# 8-Solenoid-Schematic.net
KiCad netlist of a schematic drawn in Altium Designer
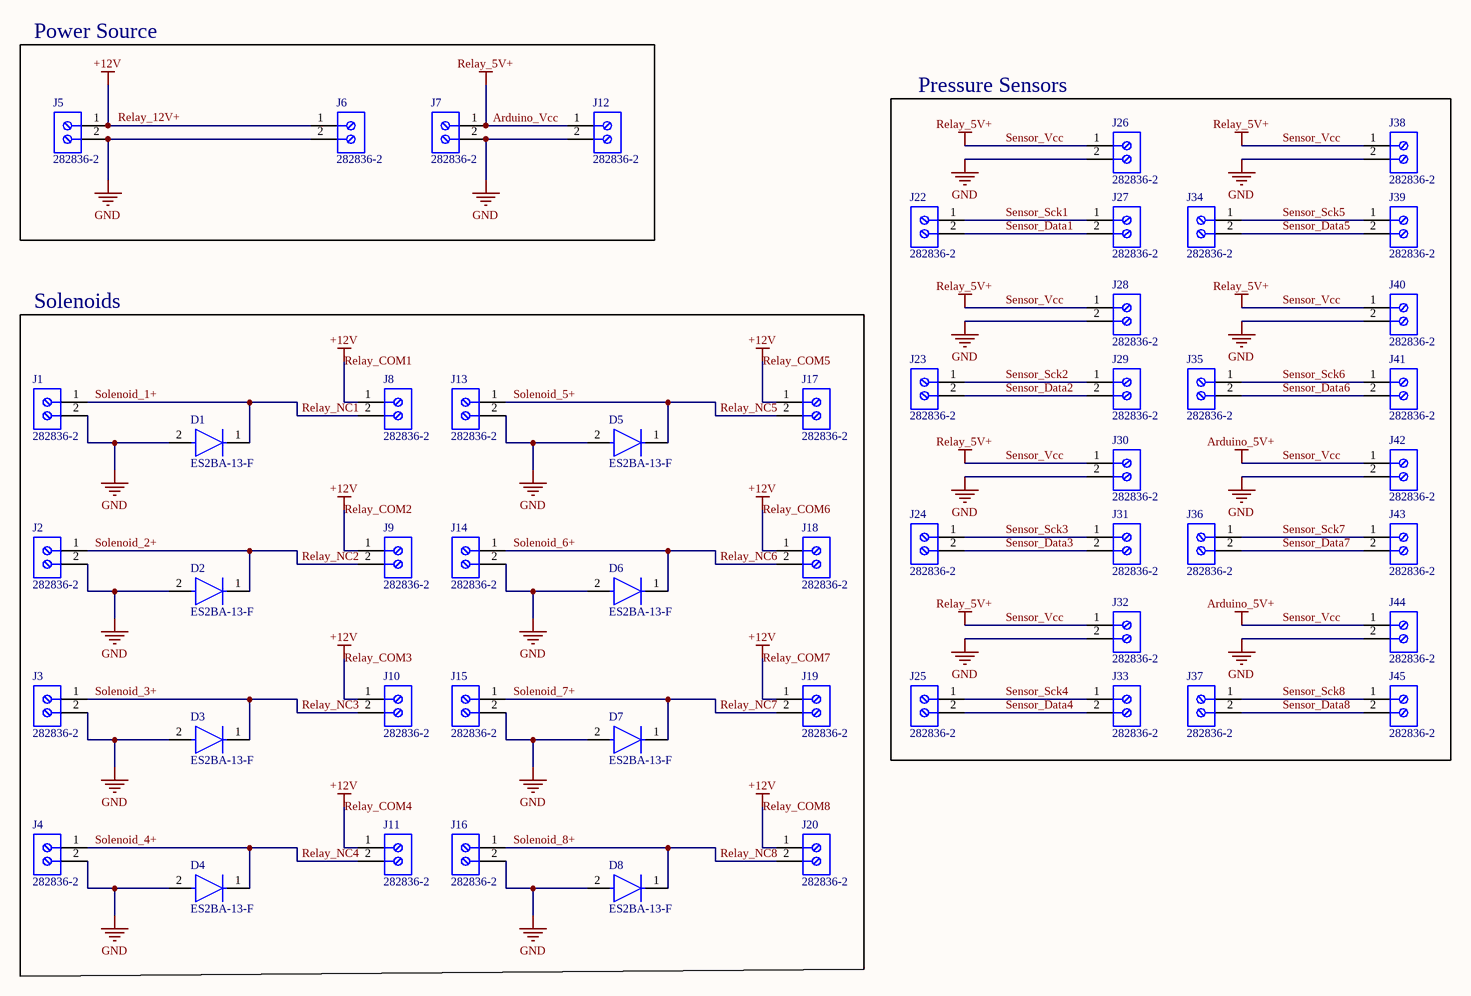
[diagram p0: 8-Solenoid-Schematic.SchDoc]

(export (version "E")
  (design (tool "Eeschema 10.0.6"))
  (components
    (comp (ref "D1")
      (value "ES2BA-13-F")
      (footprint "FP-SMA-MFG")
      (description "DIODE GEN PURP 100V 2A SMA")
      (fields
        (field (name "MANUFACTURER") "Diodes Inc.")
        (field (name "OCTOPART") "https://octopart.com/es2ba-13-f-diodes+inc.-14402013")
      )
      (libsource (lib "Altium Content Vault") (part "d7152d700b627762746794eb795d46e"))
    )
    (comp (ref "D2")
      (value "ES2BA-13-F")
      (footprint "FP-SMA-MFG")
      (description "DIODE GEN PURP 100V 2A SMA")
      (fields
        (field (name "MANUFACTURER") "Diodes Inc.")
        (field (name "OCTOPART") "https://octopart.com/es2ba-13-f-diodes+inc.-14402013")
      )
      (libsource (lib "Altium Content Vault") (part "d7152d700b627762746794eb795d46e"))
    )
    (comp (ref "D3")
      (value "ES2BA-13-F")
      (footprint "FP-SMA-MFG")
      (description "DIODE GEN PURP 100V 2A SMA")
      (fields
        (field (name "MANUFACTURER") "Diodes Inc.")
        (field (name "OCTOPART") "https://octopart.com/es2ba-13-f-diodes+inc.-14402013")
      )
      (libsource (lib "Altium Content Vault") (part "d7152d700b627762746794eb795d46e"))
    )
    (comp (ref "D4")
      (value "ES2BA-13-F")
      (footprint "FP-SMA-MFG")
      (description "DIODE GEN PURP 100V 2A SMA")
      (fields
        (field (name "MANUFACTURER") "Diodes Inc.")
        (field (name "OCTOPART") "https://octopart.com/es2ba-13-f-diodes+inc.-14402013")
      )
      (libsource (lib "Altium Content Vault") (part "d7152d700b627762746794eb795d46e"))
    )
    (comp (ref "D5")
      (value "ES2BA-13-F")
      (footprint "FP-SMA-MFG")
      (description "DIODE GEN PURP 100V 2A SMA")
      (fields
        (field (name "MANUFACTURER") "Diodes Inc.")
        (field (name "OCTOPART") "https://octopart.com/es2ba-13-f-diodes+inc.-14402013")
      )
      (libsource (lib "Altium Content Vault") (part "d7152d700b627762746794eb795d46e"))
    )
    (comp (ref "D6")
      (value "ES2BA-13-F")
      (footprint "FP-SMA-MFG")
      (description "DIODE GEN PURP 100V 2A SMA")
      (fields
        (field (name "MANUFACTURER") "Diodes Inc.")
        (field (name "OCTOPART") "https://octopart.com/es2ba-13-f-diodes+inc.-14402013")
      )
      (libsource (lib "Altium Content Vault") (part "d7152d700b627762746794eb795d46e"))
    )
    (comp (ref "D7")
      (value "ES2BA-13-F")
      (footprint "FP-SMA-MFG")
      (description "DIODE GEN PURP 100V 2A SMA")
      (fields
        (field (name "MANUFACTURER") "Diodes Inc.")
        (field (name "OCTOPART") "https://octopart.com/es2ba-13-f-diodes+inc.-14402013")
      )
      (libsource (lib "Altium Content Vault") (part "d7152d700b627762746794eb795d46e"))
    )
    (comp (ref "D8")
      (value "ES2BA-13-F")
      (footprint "FP-SMA-MFG")
      (description "DIODE GEN PURP 100V 2A SMA")
      (fields
        (field (name "MANUFACTURER") "Diodes Inc.")
        (field (name "OCTOPART") "https://octopart.com/es2ba-13-f-diodes+inc.-14402013")
      )
      (libsource (lib "Altium Content Vault") (part "d7152d700b627762746794eb795d46e"))
    )
    (comp (ref "J1")
      (value "282836-2")
      (footprint "TECO-282836-2_V")
      (description "Female Header, Pitch 5 mm, 1 x 2 Position, Height 10 mm, Tail Length 3.5 mm, Rohs, Bulk")
      (fields (field (name "VOLTAGE") "300V") (field (name "MANUFACTURER") "TE Connectivity"))
      (libsource (lib "Altium Content Vault") (part "CN-1P-F-TB2"))
    )
    (comp (ref "J2")
      (value "282836-2")
      (footprint "TECO-282836-2_V")
      (description "Female Header, Pitch 5 mm, 1 x 2 Position, Height 10 mm, Tail Length 3.5 mm, Rohs, Bulk")
      (fields (field (name "VOLTAGE") "300V") (field (name "MANUFACTURER") "TE Connectivity"))
      (libsource (lib "Altium Content Vault") (part "CN-1P-F-TB2"))
    )
    (comp (ref "J3")
      (value "282836-2")
      (footprint "TECO-282836-2_V")
      (description "Female Header, Pitch 5 mm, 1 x 2 Position, Height 10 mm, Tail Length 3.5 mm, Rohs, Bulk")
      (fields (field (name "VOLTAGE") "300V") (field (name "MANUFACTURER") "TE Connectivity"))
      (libsource (lib "Altium Content Vault") (part "CN-1P-F-TB2"))
    )
    (comp (ref "J4")
      (value "282836-2")
      (footprint "TECO-282836-2_V")
      (description "Female Header, Pitch 5 mm, 1 x 2 Position, Height 10 mm, Tail Length 3.5 mm, Rohs, Bulk")
      (fields (field (name "VOLTAGE") "300V") (field (name "MANUFACTURER") "TE Connectivity"))
      (libsource (lib "Altium Content Vault") (part "CN-1P-F-TB2"))
    )
    (comp (ref "J5")
      (value "282836-2")
      (footprint "TECO-282836-2_V")
      (description "Female Header, Pitch 5 mm, 1 x 2 Position, Height 10 mm, Tail Length 3.5 mm, Rohs, Bulk")
      (fields (field (name "VOLTAGE") "300V") (field (name "MANUFACTURER") "TE Connectivity"))
      (libsource (lib "Altium Content Vault") (part "CN-1P-F-TB2"))
    )
    (comp (ref "J6")
      (value "282836-2")
      (footprint "TECO-282836-2_V")
      (description "Female Header, Pitch 5 mm, 1 x 2 Position, Height 10 mm, Tail Length 3.5 mm, Rohs, Bulk")
      (fields (field (name "VOLTAGE") "300V") (field (name "MANUFACTURER") "TE Connectivity"))
      (libsource (lib "Altium Content Vault") (part "CN-1P-F-TB2"))
    )
    (comp (ref "J7")
      (value "282836-2")
      (footprint "TECO-282836-2_V")
      (description "Female Header, Pitch 5 mm, 1 x 2 Position, Height 10 mm, Tail Length 3.5 mm, Rohs, Bulk")
      (fields (field (name "VOLTAGE") "300V") (field (name "MANUFACTURER") "TE Connectivity"))
      (libsource (lib "Altium Content Vault") (part "CN-1P-F-TB2"))
    )
    (comp (ref "J8")
      (value "282836-2")
      (footprint "TECO-282836-2_V")
      (description "Female Header, Pitch 5 mm, 1 x 2 Position, Height 10 mm, Tail Length 3.5 mm, Rohs, Bulk")
      (fields (field (name "VOLTAGE") "300V") (field (name "MANUFACTURER") "TE Connectivity"))
      (libsource (lib "Altium Content Vault") (part "CN-1P-F-TB2"))
    )
    (comp (ref "J9")
      (value "282836-2")
      (footprint "TECO-282836-2_V")
      (description "Female Header, Pitch 5 mm, 1 x 2 Position, Height 10 mm, Tail Length 3.5 mm, Rohs, Bulk")
      (fields (field (name "VOLTAGE") "300V") (field (name "MANUFACTURER") "TE Connectivity"))
      (libsource (lib "Altium Content Vault") (part "CN-1P-F-TB2"))
    )
    (comp (ref "J10")
      (value "282836-2")
      (footprint "TECO-282836-2_V")
      (description "Female Header, Pitch 5 mm, 1 x 2 Position, Height 10 mm, Tail Length 3.5 mm, Rohs, Bulk")
      (fields (field (name "VOLTAGE") "300V") (field (name "MANUFACTURER") "TE Connectivity"))
      (libsource (lib "Altium Content Vault") (part "CN-1P-F-TB2"))
    )
    (comp (ref "J11")
      (value "282836-2")
      (footprint "TECO-282836-2_V")
      (description "Female Header, Pitch 5 mm, 1 x 2 Position, Height 10 mm, Tail Length 3.5 mm, Rohs, Bulk")
      (fields (field (name "VOLTAGE") "300V") (field (name "MANUFACTURER") "TE Connectivity"))
      (libsource (lib "Altium Content Vault") (part "CN-1P-F-TB2"))
    )
    (comp (ref "J12")
      (value "282836-2")
      (footprint "TECO-282836-2_V")
      (description "Female Header, Pitch 5 mm, 1 x 2 Position, Height 10 mm, Tail Length 3.5 mm, Rohs, Bulk")
      (fields (field (name "VOLTAGE") "300V") (field (name "MANUFACTURER") "TE Connectivity"))
      (libsource (lib "Altium Content Vault") (part "CN-1P-F-TB2"))
    )
    (comp (ref "J13")
      (value "282836-2")
      (footprint "TECO-282836-2_V")
      (description "Female Header, Pitch 5 mm, 1 x 2 Position, Height 10 mm, Tail Length 3.5 mm, Rohs, Bulk")
      (fields (field (name "VOLTAGE") "300V") (field (name "MANUFACTURER") "TE Connectivity"))
      (libsource (lib "Altium Content Vault") (part "CN-1P-F-TB2"))
    )
    (comp (ref "J14")
      (value "282836-2")
      (footprint "TECO-282836-2_V")
      (description "Female Header, Pitch 5 mm, 1 x 2 Position, Height 10 mm, Tail Length 3.5 mm, Rohs, Bulk")
      (fields (field (name "VOLTAGE") "300V") (field (name "MANUFACTURER") "TE Connectivity"))
      (libsource (lib "Altium Content Vault") (part "CN-1P-F-TB2"))
    )
    (comp (ref "J15")
      (value "282836-2")
      (footprint "TECO-282836-2_V")
      (description "Female Header, Pitch 5 mm, 1 x 2 Position, Height 10 mm, Tail Length 3.5 mm, Rohs, Bulk")
      (fields (field (name "VOLTAGE") "300V") (field (name "MANUFACTURER") "TE Connectivity"))
      (libsource (lib "Altium Content Vault") (part "CN-1P-F-TB2"))
    )
    (comp (ref "J16")
      (value "282836-2")
      (footprint "TECO-282836-2_V")
      (description "Female Header, Pitch 5 mm, 1 x 2 Position, Height 10 mm, Tail Length 3.5 mm, Rohs, Bulk")
      (fields (field (name "VOLTAGE") "300V") (field (name "MANUFACTURER") "TE Connectivity"))
      (libsource (lib "Altium Content Vault") (part "CN-1P-F-TB2"))
    )
    (comp (ref "J17")
      (value "282836-2")
      (footprint "TECO-282836-2_V")
      (description "Female Header, Pitch 5 mm, 1 x 2 Position, Height 10 mm, Tail Length 3.5 mm, Rohs, Bulk")
      (fields (field (name "VOLTAGE") "300V") (field (name "MANUFACTURER") "TE Connectivity"))
      (libsource (lib "Altium Content Vault") (part "CN-1P-F-TB2"))
    )
    (comp (ref "J18")
      (value "282836-2")
      (footprint "TECO-282836-2_V")
      (description "Female Header, Pitch 5 mm, 1 x 2 Position, Height 10 mm, Tail Length 3.5 mm, Rohs, Bulk")
      (fields (field (name "VOLTAGE") "300V") (field (name "MANUFACTURER") "TE Connectivity"))
      (libsource (lib "Altium Content Vault") (part "CN-1P-F-TB2"))
    )
    (comp (ref "J19")
      (value "282836-2")
      (footprint "TECO-282836-2_V")
      (description "Female Header, Pitch 5 mm, 1 x 2 Position, Height 10 mm, Tail Length 3.5 mm, Rohs, Bulk")
      (fields (field (name "VOLTAGE") "300V") (field (name "MANUFACTURER") "TE Connectivity"))
      (libsource (lib "Altium Content Vault") (part "CN-1P-F-TB2"))
    )
    (comp (ref "J20")
      (value "282836-2")
      (footprint "TECO-282836-2_V")
      (description "Female Header, Pitch 5 mm, 1 x 2 Position, Height 10 mm, Tail Length 3.5 mm, Rohs, Bulk")
      (fields (field (name "VOLTAGE") "300V") (field (name "MANUFACTURER") "TE Connectivity"))
      (libsource (lib "Altium Content Vault") (part "CN-1P-F-TB2"))
    )
    (comp (ref "J22")
      (value "282836-2")
      (footprint "TECO-282836-2_V")
      (description "Female Header, Pitch 5 mm, 1 x 2 Position, Height 10 mm, Tail Length 3.5 mm, Rohs, Bulk")
      (fields (field (name "VOLTAGE") "300V") (field (name "MANUFACTURER") "TE Connectivity"))
      (libsource (lib "Altium Content Vault") (part "CN-1P-F-TB2"))
    )
    (comp (ref "J23")
      (value "282836-2")
      (footprint "TECO-282836-2_V")
      (description "Female Header, Pitch 5 mm, 1 x 2 Position, Height 10 mm, Tail Length 3.5 mm, Rohs, Bulk")
      (fields (field (name "VOLTAGE") "300V") (field (name "MANUFACTURER") "TE Connectivity"))
      (libsource (lib "Altium Content Vault") (part "CN-1P-F-TB2"))
    )
    (comp (ref "J24")
      (value "282836-2")
      (footprint "TECO-282836-2_V")
      (description "Female Header, Pitch 5 mm, 1 x 2 Position, Height 10 mm, Tail Length 3.5 mm, Rohs, Bulk")
      (fields (field (name "VOLTAGE") "300V") (field (name "MANUFACTURER") "TE Connectivity"))
      (libsource (lib "Altium Content Vault") (part "CN-1P-F-TB2"))
    )
    (comp (ref "J25")
      (value "282836-2")
      (footprint "TECO-282836-2_V")
      (description "Female Header, Pitch 5 mm, 1 x 2 Position, Height 10 mm, Tail Length 3.5 mm, Rohs, Bulk")
      (fields (field (name "VOLTAGE") "300V") (field (name "MANUFACTURER") "TE Connectivity"))
      (libsource (lib "Altium Content Vault") (part "CN-1P-F-TB2"))
    )
    (comp (ref "J26")
      (value "282836-2")
      (footprint "TECO-282836-2_V")
      (description "Female Header, Pitch 5 mm, 1 x 2 Position, Height 10 mm, Tail Length 3.5 mm, Rohs, Bulk")
      (fields (field (name "VOLTAGE") "300V") (field (name "MANUFACTURER") "TE Connectivity"))
      (libsource (lib "Altium Content Vault") (part "CN-1P-F-TB2"))
    )
    (comp (ref "J27")
      (value "282836-2")
      (footprint "TECO-282836-2_V")
      (description "Female Header, Pitch 5 mm, 1 x 2 Position, Height 10 mm, Tail Length 3.5 mm, Rohs, Bulk")
      (fields (field (name "VOLTAGE") "300V") (field (name "MANUFACTURER") "TE Connectivity"))
      (libsource (lib "Altium Content Vault") (part "CN-1P-F-TB2"))
    )
    (comp (ref "J28")
      (value "282836-2")
      (footprint "TECO-282836-2_V")
      (description "Female Header, Pitch 5 mm, 1 x 2 Position, Height 10 mm, Tail Length 3.5 mm, Rohs, Bulk")
      (fields (field (name "VOLTAGE") "300V") (field (name "MANUFACTURER") "TE Connectivity"))
      (libsource (lib "Altium Content Vault") (part "CN-1P-F-TB2"))
    )
    (comp (ref "J29")
      (value "282836-2")
      (footprint "TECO-282836-2_V")
      (description "Female Header, Pitch 5 mm, 1 x 2 Position, Height 10 mm, Tail Length 3.5 mm, Rohs, Bulk")
      (fields (field (name "VOLTAGE") "300V") (field (name "MANUFACTURER") "TE Connectivity"))
      (libsource (lib "Altium Content Vault") (part "CN-1P-F-TB2"))
    )
    (comp (ref "J30")
      (value "282836-2")
      (footprint "TECO-282836-2_V")
      (description "Female Header, Pitch 5 mm, 1 x 2 Position, Height 10 mm, Tail Length 3.5 mm, Rohs, Bulk")
      (fields (field (name "VOLTAGE") "300V") (field (name "MANUFACTURER") "TE Connectivity"))
      (libsource (lib "Altium Content Vault") (part "CN-1P-F-TB2"))
    )
    (comp (ref "J31")
      (value "282836-2")
      (footprint "TECO-282836-2_V")
      (description "Female Header, Pitch 5 mm, 1 x 2 Position, Height 10 mm, Tail Length 3.5 mm, Rohs, Bulk")
      (fields (field (name "VOLTAGE") "300V") (field (name "MANUFACTURER") "TE Connectivity"))
      (libsource (lib "Altium Content Vault") (part "CN-1P-F-TB2"))
    )
    (comp (ref "J32")
      (value "282836-2")
      (footprint "TECO-282836-2_V")
      (description "Female Header, Pitch 5 mm, 1 x 2 Position, Height 10 mm, Tail Length 3.5 mm, Rohs, Bulk")
      (fields (field (name "VOLTAGE") "300V") (field (name "MANUFACTURER") "TE Connectivity"))
      (libsource (lib "Altium Content Vault") (part "CN-1P-F-TB2"))
    )
    (comp (ref "J33")
      (value "282836-2")
      (footprint "TECO-282836-2_V")
      (description "Female Header, Pitch 5 mm, 1 x 2 Position, Height 10 mm, Tail Length 3.5 mm, Rohs, Bulk")
      (fields (field (name "VOLTAGE") "300V") (field (name "MANUFACTURER") "TE Connectivity"))
      (libsource (lib "Altium Content Vault") (part "CN-1P-F-TB2"))
    )
    (comp (ref "J34")
      (value "282836-2")
      (footprint "TECO-282836-2_V")
      (description "Female Header, Pitch 5 mm, 1 x 2 Position, Height 10 mm, Tail Length 3.5 mm, Rohs, Bulk")
      (fields (field (name "VOLTAGE") "300V") (field (name "MANUFACTURER") "TE Connectivity"))
      (libsource (lib "Altium Content Vault") (part "CN-1P-F-TB2"))
    )
    (comp (ref "J35")
      (value "282836-2")
      (footprint "TECO-282836-2_V")
      (description "Female Header, Pitch 5 mm, 1 x 2 Position, Height 10 mm, Tail Length 3.5 mm, Rohs, Bulk")
      (fields (field (name "VOLTAGE") "300V") (field (name "MANUFACTURER") "TE Connectivity"))
      (libsource (lib "Altium Content Vault") (part "CN-1P-F-TB2"))
    )
    (comp (ref "J36")
      (value "282836-2")
      (footprint "TECO-282836-2_V")
      (description "Female Header, Pitch 5 mm, 1 x 2 Position, Height 10 mm, Tail Length 3.5 mm, Rohs, Bulk")
      (fields (field (name "VOLTAGE") "300V") (field (name "MANUFACTURER") "TE Connectivity"))
      (libsource (lib "Altium Content Vault") (part "CN-1P-F-TB2"))
    )
    (comp (ref "J37")
      (value "282836-2")
      (footprint "TECO-282836-2_V")
      (description "Female Header, Pitch 5 mm, 1 x 2 Position, Height 10 mm, Tail Length 3.5 mm, Rohs, Bulk")
      (fields (field (name "VOLTAGE") "300V") (field (name "MANUFACTURER") "TE Connectivity"))
      (libsource (lib "Altium Content Vault") (part "CN-1P-F-TB2"))
    )
    (comp (ref "J38")
      (value "282836-2")
      (footprint "TECO-282836-2_V")
      (description "Female Header, Pitch 5 mm, 1 x 2 Position, Height 10 mm, Tail Length 3.5 mm, Rohs, Bulk")
      (fields (field (name "VOLTAGE") "300V") (field (name "MANUFACTURER") "TE Connectivity"))
      (libsource (lib "Altium Content Vault") (part "CN-1P-F-TB2"))
    )
    (comp (ref "J39")
      (value "282836-2")
      (footprint "TECO-282836-2_V")
      (description "Female Header, Pitch 5 mm, 1 x 2 Position, Height 10 mm, Tail Length 3.5 mm, Rohs, Bulk")
      (fields (field (name "VOLTAGE") "300V") (field (name "MANUFACTURER") "TE Connectivity"))
      (libsource (lib "Altium Content Vault") (part "CN-1P-F-TB2"))
    )
    (comp (ref "J40")
      (value "282836-2")
      (footprint "TECO-282836-2_V")
      (description "Female Header, Pitch 5 mm, 1 x 2 Position, Height 10 mm, Tail Length 3.5 mm, Rohs, Bulk")
      (fields (field (name "VOLTAGE") "300V") (field (name "MANUFACTURER") "TE Connectivity"))
      (libsource (lib "Altium Content Vault") (part "CN-1P-F-TB2"))
    )
    (comp (ref "J41")
      (value "282836-2")
      (footprint "TECO-282836-2_V")
      (description "Female Header, Pitch 5 mm, 1 x 2 Position, Height 10 mm, Tail Length 3.5 mm, Rohs, Bulk")
      (fields (field (name "VOLTAGE") "300V") (field (name "MANUFACTURER") "TE Connectivity"))
      (libsource (lib "Altium Content Vault") (part "CN-1P-F-TB2"))
    )
    (comp (ref "J42")
      (value "282836-2")
      (footprint "TECO-282836-2_V")
      (description "Female Header, Pitch 5 mm, 1 x 2 Position, Height 10 mm, Tail Length 3.5 mm, Rohs, Bulk")
      (fields (field (name "VOLTAGE") "300V") (field (name "MANUFACTURER") "TE Connectivity"))
      (libsource (lib "Altium Content Vault") (part "CN-1P-F-TB2"))
    )
    (comp (ref "J43")
      (value "282836-2")
      (footprint "TECO-282836-2_V")
      (description "Female Header, Pitch 5 mm, 1 x 2 Position, Height 10 mm, Tail Length 3.5 mm, Rohs, Bulk")
      (fields (field (name "VOLTAGE") "300V") (field (name "MANUFACTURER") "TE Connectivity"))
      (libsource (lib "Altium Content Vault") (part "CN-1P-F-TB2"))
    )
    (comp (ref "J44")
      (value "282836-2")
      (footprint "TECO-282836-2_V")
      (description "Female Header, Pitch 5 mm, 1 x 2 Position, Height 10 mm, Tail Length 3.5 mm, Rohs, Bulk")
      (fields (field (name "VOLTAGE") "300V") (field (name "MANUFACTURER") "TE Connectivity"))
      (libsource (lib "Altium Content Vault") (part "CN-1P-F-TB2"))
    )
    (comp (ref "J45")
      (value "282836-2")
      (footprint "TECO-282836-2_V")
      (description "Female Header, Pitch 5 mm, 1 x 2 Position, Height 10 mm, Tail Length 3.5 mm, Rohs, Bulk")
      (fields (field (name "VOLTAGE") "300V") (field (name "MANUFACTURER") "TE Connectivity"))
      (libsource (lib "Altium Content Vault") (part "CN-1P-F-TB2"))
    )
  )
  (nets
    (net (code "1") (name "+12V") (class "Default")
      (node (ref "J10") (pin "1") (pinfunction "1_1") (pintype "passive"))
      (node (ref "J11") (pin "1") (pinfunction "1_1") (pintype "passive"))
      (node (ref "J17") (pin "1") (pinfunction "1_1") (pintype "passive"))
      (node (ref "J18") (pin "1") (pinfunction "1_1") (pintype "passive"))
      (node (ref "J19") (pin "1") (pinfunction "1_1") (pintype "passive"))
      (node (ref "J20") (pin "1") (pinfunction "1_1") (pintype "passive"))
      (node (ref "J5") (pin "1") (pinfunction "1_1") (pintype "passive"))
      (node (ref "J6") (pin "1") (pinfunction "1_1") (pintype "passive"))
      (node (ref "J8") (pin "1") (pinfunction "1_1") (pintype "passive"))
      (node (ref "J9") (pin "1") (pinfunction "1_1") (pintype "passive"))
    )
    (net (code "3") (name "/Relay_NC1") (class "Default")
      (node (ref "D1") (pin "1") (pinfunction "C_1") (pintype "passive"))
      (node (ref "J1") (pin "1") (pinfunction "1_1") (pintype "passive"))
      (node (ref "J8") (pin "2") (pinfunction "2_2") (pintype "passive"))
    )
    (net (code "4") (name "/Relay_NC2") (class "Default")
      (node (ref "D2") (pin "1") (pinfunction "C_1") (pintype "passive"))
      (node (ref "J2") (pin "1") (pinfunction "1_1") (pintype "passive"))
      (node (ref "J9") (pin "2") (pinfunction "2_2") (pintype "passive"))
    )
    (net (code "5") (name "/Relay_NC3") (class "Default")
      (node (ref "D3") (pin "1") (pinfunction "C_1") (pintype "passive"))
      (node (ref "J10") (pin "2") (pinfunction "2_2") (pintype "passive"))
      (node (ref "J3") (pin "1") (pinfunction "1_1") (pintype "passive"))
    )
    (net (code "6") (name "/Relay_NC4") (class "Default")
      (node (ref "D4") (pin "1") (pinfunction "C_1") (pintype "passive"))
      (node (ref "J11") (pin "2") (pinfunction "2_2") (pintype "passive"))
      (node (ref "J4") (pin "1") (pinfunction "1_1") (pintype "passive"))
    )
    (net (code "7") (name "/Relay_NC5") (class "Default")
      (node (ref "D5") (pin "1") (pinfunction "C_1") (pintype "passive"))
      (node (ref "J13") (pin "1") (pinfunction "1_1") (pintype "passive"))
      (node (ref "J17") (pin "2") (pinfunction "2_2") (pintype "passive"))
    )
    (net (code "8") (name "/Relay_NC6") (class "Default")
      (node (ref "D6") (pin "1") (pinfunction "C_1") (pintype "passive"))
      (node (ref "J14") (pin "1") (pinfunction "1_1") (pintype "passive"))
      (node (ref "J18") (pin "2") (pinfunction "2_2") (pintype "passive"))
    )
    (net (code "9") (name "/Relay_NC7") (class "Default")
      (node (ref "D7") (pin "1") (pinfunction "C_1") (pintype "passive"))
      (node (ref "J15") (pin "1") (pinfunction "1_1") (pintype "passive"))
      (node (ref "J19") (pin "2") (pinfunction "2_2") (pintype "passive"))
    )
    (net (code "10") (name "/Relay_NC8") (class "Default")
      (node (ref "D8") (pin "1") (pinfunction "C_1") (pintype "passive"))
      (node (ref "J16") (pin "1") (pinfunction "1_1") (pintype "passive"))
      (node (ref "J20") (pin "2") (pinfunction "2_2") (pintype "passive"))
    )
    (net (code "11") (name "/Sensor_Data1") (class "Default")
      (node (ref "J22") (pin "2") (pinfunction "2_2") (pintype "passive"))
      (node (ref "J27") (pin "2") (pinfunction "2_2") (pintype "passive"))
    )
    (net (code "12") (name "/Sensor_Data2") (class "Default")
      (node (ref "J23") (pin "2") (pinfunction "2_2") (pintype "passive"))
      (node (ref "J29") (pin "2") (pinfunction "2_2") (pintype "passive"))
    )
    (net (code "13") (name "/Sensor_Data3") (class "Default")
      (node (ref "J24") (pin "2") (pinfunction "2_2") (pintype "passive"))
      (node (ref "J31") (pin "2") (pinfunction "2_2") (pintype "passive"))
    )
    (net (code "14") (name "/Sensor_Data4") (class "Default")
      (node (ref "J25") (pin "2") (pinfunction "2_2") (pintype "passive"))
      (node (ref "J33") (pin "2") (pinfunction "2_2") (pintype "passive"))
    )
    (net (code "15") (name "/Sensor_Data5") (class "Default")
      (node (ref "J34") (pin "2") (pinfunction "2_2") (pintype "passive"))
      (node (ref "J39") (pin "2") (pinfunction "2_2") (pintype "passive"))
    )
    (net (code "16") (name "/Sensor_Data6") (class "Default")
      (node (ref "J35") (pin "2") (pinfunction "2_2") (pintype "passive"))
      (node (ref "J41") (pin "2") (pinfunction "2_2") (pintype "passive"))
    )
    (net (code "17") (name "/Sensor_Data7") (class "Default")
      (node (ref "J36") (pin "2") (pinfunction "2_2") (pintype "passive"))
      (node (ref "J43") (pin "2") (pinfunction "2_2") (pintype "passive"))
    )
    (net (code "18") (name "/Sensor_Data8") (class "Default")
      (node (ref "J37") (pin "2") (pinfunction "2_2") (pintype "passive"))
      (node (ref "J45") (pin "2") (pinfunction "2_2") (pintype "passive"))
    )
    (net (code "19") (name "/Sensor_Sck1") (class "Default")
      (node (ref "J22") (pin "1") (pinfunction "1_1") (pintype "passive"))
      (node (ref "J27") (pin "1") (pinfunction "1_1") (pintype "passive"))
    )
    (net (code "20") (name "/Sensor_Sck2") (class "Default")
      (node (ref "J23") (pin "1") (pinfunction "1_1") (pintype "passive"))
      (node (ref "J29") (pin "1") (pinfunction "1_1") (pintype "passive"))
    )
    (net (code "21") (name "/Sensor_Sck3") (class "Default")
      (node (ref "J24") (pin "1") (pinfunction "1_1") (pintype "passive"))
      (node (ref "J31") (pin "1") (pinfunction "1_1") (pintype "passive"))
    )
    (net (code "22") (name "/Sensor_Sck4") (class "Default")
      (node (ref "J25") (pin "1") (pinfunction "1_1") (pintype "passive"))
      (node (ref "J33") (pin "1") (pinfunction "1_1") (pintype "passive"))
    )
    (net (code "23") (name "/Sensor_Sck5") (class "Default")
      (node (ref "J34") (pin "1") (pinfunction "1_1") (pintype "passive"))
      (node (ref "J39") (pin "1") (pinfunction "1_1") (pintype "passive"))
    )
    (net (code "24") (name "/Sensor_Sck6") (class "Default")
      (node (ref "J35") (pin "1") (pinfunction "1_1") (pintype "passive"))
      (node (ref "J41") (pin "1") (pinfunction "1_1") (pintype "passive"))
    )
    (net (code "25") (name "/Sensor_Sck7") (class "Default")
      (node (ref "J36") (pin "1") (pinfunction "1_1") (pintype "passive"))
      (node (ref "J43") (pin "1") (pinfunction "1_1") (pintype "passive"))
    )
    (net (code "26") (name "/Sensor_Sck8") (class "Default")
      (node (ref "J37") (pin "1") (pinfunction "1_1") (pintype "passive"))
      (node (ref "J45") (pin "1") (pinfunction "1_1") (pintype "passive"))
    )
    (net (code "27") (name "Arduino_5V+") (class "Default")
      (node (ref "J12") (pin "1") (pinfunction "1_1") (pintype "passive"))
      (node (ref "J26") (pin "1") (pinfunction "1_1") (pintype "passive"))
      (node (ref "J28") (pin "1") (pinfunction "1_1") (pintype "passive"))
      (node (ref "J30") (pin "1") (pinfunction "1_1") (pintype "passive"))
      (node (ref "J32") (pin "1") (pinfunction "1_1") (pintype "passive"))
      (node (ref "J38") (pin "1") (pinfunction "1_1") (pintype "passive"))
      (node (ref "J40") (pin "1") (pinfunction "1_1") (pintype "passive"))
      (node (ref "J42") (pin "1") (pinfunction "1_1") (pintype "passive"))
      (node (ref "J44") (pin "1") (pinfunction "1_1") (pintype "passive"))
      (node (ref "J7") (pin "1") (pinfunction "1_1") (pintype "passive"))
    )
    (net (code "28") (name "GND") (class "Default")
      (node (ref "D1") (pin "2") (pinfunction "A_2") (pintype "passive"))
      (node (ref "D2") (pin "2") (pinfunction "A_2") (pintype "passive"))
      (node (ref "D3") (pin "2") (pinfunction "A_2") (pintype "passive"))
      (node (ref "D4") (pin "2") (pinfunction "A_2") (pintype "passive"))
      (node (ref "D5") (pin "2") (pinfunction "A_2") (pintype "passive"))
      (node (ref "D6") (pin "2") (pinfunction "A_2") (pintype "passive"))
      (node (ref "D7") (pin "2") (pinfunction "A_2") (pintype "passive"))
      (node (ref "D8") (pin "2") (pinfunction "A_2") (pintype "passive"))
      (node (ref "J1") (pin "2") (pinfunction "2_2") (pintype "passive"))
      (node (ref "J12") (pin "2") (pinfunction "2_2") (pintype "passive"))
      (node (ref "J13") (pin "2") (pinfunction "2_2") (pintype "passive"))
      (node (ref "J14") (pin "2") (pinfunction "2_2") (pintype "passive"))
      (node (ref "J15") (pin "2") (pinfunction "2_2") (pintype "passive"))
      (node (ref "J16") (pin "2") (pinfunction "2_2") (pintype "passive"))
      (node (ref "J2") (pin "2") (pinfunction "2_2") (pintype "passive"))
      (node (ref "J26") (pin "2") (pinfunction "2_2") (pintype "passive"))
      (node (ref "J28") (pin "2") (pinfunction "2_2") (pintype "passive"))
      (node (ref "J3") (pin "2") (pinfunction "2_2") (pintype "passive"))
      (node (ref "J30") (pin "2") (pinfunction "2_2") (pintype "passive"))
      (node (ref "J32") (pin "2") (pinfunction "2_2") (pintype "passive"))
      (node (ref "J38") (pin "2") (pinfunction "2_2") (pintype "passive"))
      (node (ref "J4") (pin "2") (pinfunction "2_2") (pintype "passive"))
      (node (ref "J40") (pin "2") (pinfunction "2_2") (pintype "passive"))
      (node (ref "J42") (pin "2") (pinfunction "2_2") (pintype "passive"))
      (node (ref "J44") (pin "2") (pinfunction "2_2") (pintype "passive"))
      (node (ref "J5") (pin "2") (pinfunction "2_2") (pintype "passive"))
      (node (ref "J6") (pin "2") (pinfunction "2_2") (pintype "passive"))
      (node (ref "J7") (pin "2") (pinfunction "2_2") (pintype "passive"))
    )
  )
)
